# Power_supply.net
KiCad netlist of a schematic drawn in Altium Designer
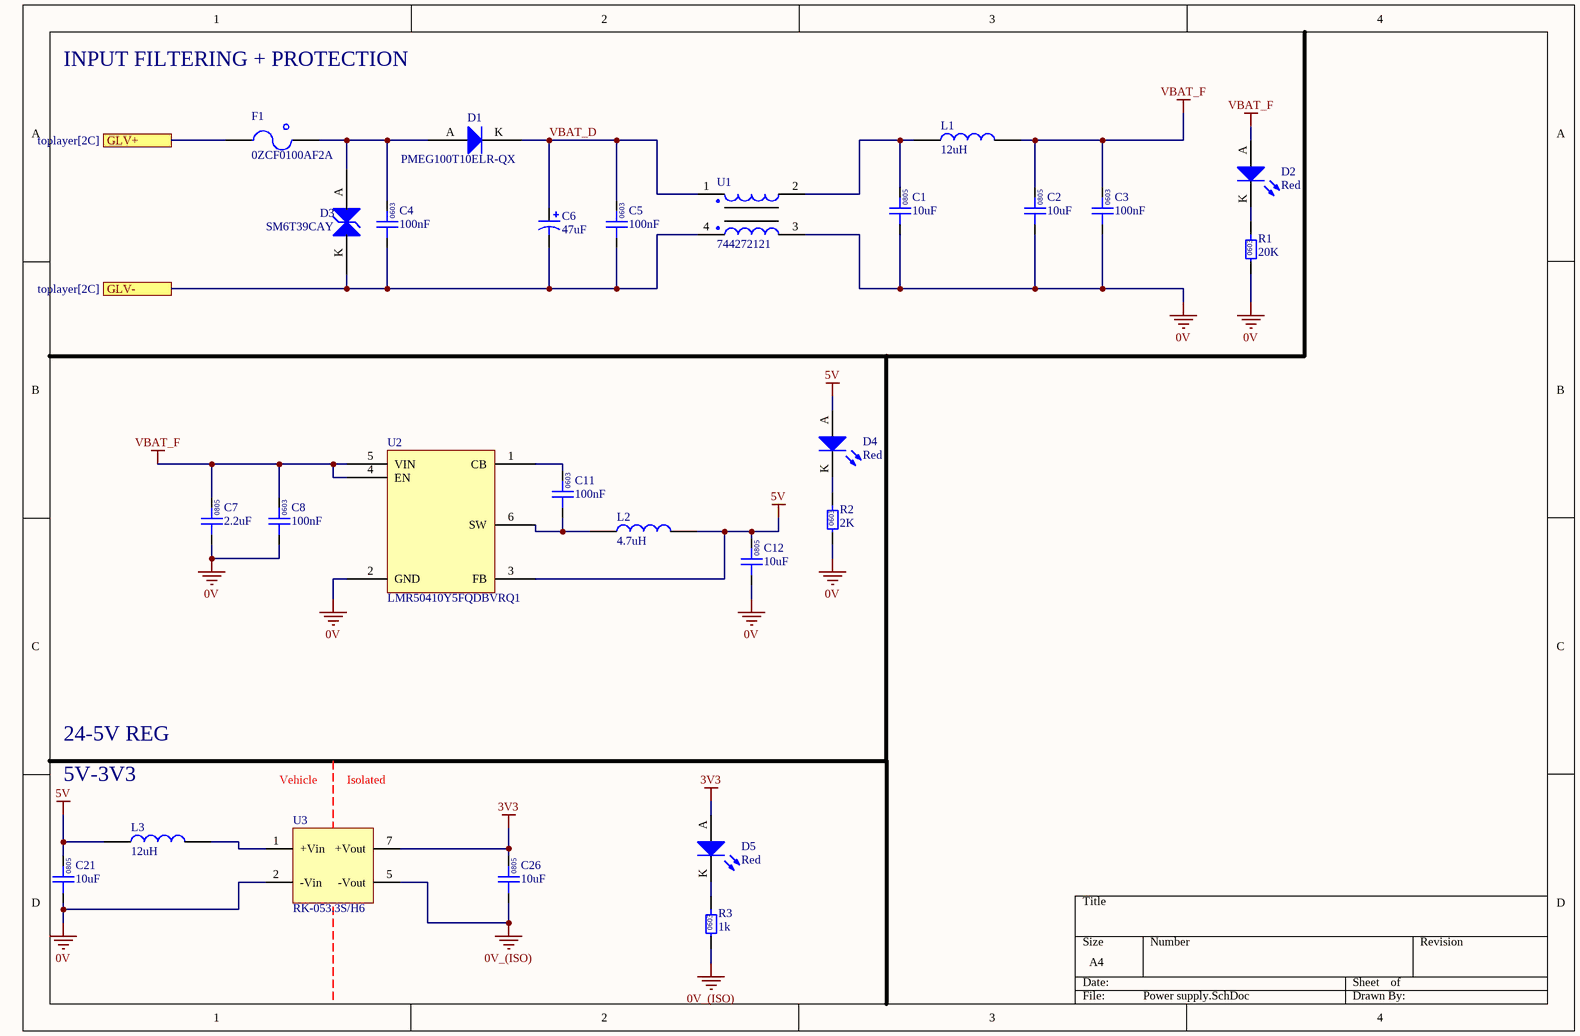
[diagram p0: Power supply.SchDoc]

(export (version "E")
  (design (tool "Eeschema 10.0.6"))
  (components
    (comp (ref "C1")
      (value "10uF")
      (footprint "0805")
      (fields
        (field (name "PART NUMBER") "GRM21BR6YA106KE43L")
        (field (name "MANUFACTURER") "muRata")
        (field (name "TOLERANCE") "10%")
      )
      (libsource (lib "ts_standard_library") (part "Capacitor 0805"))
    )
    (comp (ref "C2")
      (value "10uF")
      (footprint "0805")
      (fields
        (field (name "PART NUMBER") "GRM21BR6YA106KE43L")
        (field (name "MANUFACTURER") "muRata")
        (field (name "TOLERANCE") "10%")
      )
      (libsource (lib "ts_standard_library") (part "Capacitor 0805"))
    )
    (comp (ref "C3")
      (value "100nF")
      (footprint "0603")
      (fields
        (field (name "PART NUMBER") "GCM188L81H104KA57D")
        (field (name "MANUFACTURER") "muRata")
        (field (name "TOLERANCE") "±10%")
      )
      (libsource (lib "ts_standard_library") (part "Capacitor 0603"))
    )
    (comp (ref "C4")
      (value "100nF")
      (footprint "0603")
      (fields
        (field (name "PART NUMBER") "GCM188L81H104KA57D")
        (field (name "MANUFACTURER") "muRata")
        (field (name "TOLERANCE") "±10%")
      )
      (libsource (lib "ts_standard_library") (part "Capacitor 0603"))
    )
    (comp (ref "C5")
      (value "100nF")
      (footprint "0603")
      (fields
        (field (name "PART NUMBER") "GCM188L81H104KA57D")
        (field (name "MANUFACTURER") "muRata")
        (field (name "TOLERANCE") "±10%")
      )
      (libsource (lib "ts_standard_library") (part "Capacitor 0603"))
    )
    (comp (ref "C6")
      (value "47uF")
      (footprint "CHEMI-CON ELCO")
      (fields (field (name "PART NUMBER") "HHXA350ARA470MF61G"))
      (libsource (lib "ts_standard_library") (part "Capacitor (Polarised)"))
    )
    (comp (ref "C7")
      (value "2.2uF")
      (footprint "0805")
      (fields
        (field (name "PART NUMBER") "GRM21BR61A226ME51L")
        (field (name "MANUFACTURER") "muRata")
        (field (name "TOLERANCE") "20%")
      )
      (libsource (lib "ts_standard_library") (part "Capacitor 0805"))
    )
    (comp (ref "C8")
      (value "100nF")
      (footprint "0603")
      (fields
        (field (name "PART NUMBER") "GCM188L81H104KA57D")
        (field (name "MANUFACTURER") "muRata")
        (field (name "TOLERANCE") "±10%")
      )
      (libsource (lib "ts_standard_library") (part "Capacitor 0603"))
    )
    (comp (ref "C11")
      (value "100nF")
      (footprint "0603")
      (fields
        (field (name "PART NUMBER") "GCM188L81H104KA57D")
        (field (name "MANUFACTURER") "muRata")
        (field (name "TOLERANCE") "±10%")
      )
      (libsource (lib "ts_standard_library") (part "Capacitor 0603"))
    )
    (comp (ref "C12")
      (value "10uF")
      (footprint "0805")
      (fields
        (field (name "PART NUMBER") "GRM21BR6YA106KE43L")
        (field (name "MANUFACTURER") "muRata")
        (field (name "TOLERANCE") "10%")
      )
      (libsource (lib "ts_standard_library") (part "Capacitor 0805"))
    )
    (comp (ref "C21")
      (value "10uF")
      (footprint "0805")
      (fields
        (field (name "PART NUMBER") "GRM21BR6YA106KE43L")
        (field (name "MANUFACTURER") "muRata")
        (field (name "TOLERANCE") "10%")
      )
      (libsource (lib "ts_standard_library") (part "Capacitor 0805"))
    )
    (comp (ref "C26")
      (value "10uF")
      (footprint "0805")
      (fields
        (field (name "PART NUMBER") "GRM21BR6YA106KE43L")
        (field (name "MANUFACTURER") "muRata")
        (field (name "TOLERANCE") "10%")
      )
      (libsource (lib "ts_standard_library") (part "Capacitor 0805"))
    )
    (comp (ref "D1")
      (value "PMEG100T10ELR-QX")
      (footprint "SODFL350X110-2N")
      (description "Diode 100 V 1A Surface Mount SOD-123W")
      (libsource (lib "Team Swinburne") (part "PMEG100T10ELR-QX"))
    )
    (comp (ref "D2")
      (value "Red")
      (footprint "0805 LED")
      (description "Red LED Indication - Discrete 1.75V 0805 (2012 Metric)")
      (fields (field (name "PART NUMBER") "SML-210LTT86") (field (name "MANUFACTURER") "ROHM Semiconductor"))
      (libsource (lib "ts_standard_library") (part "LED"))
    )
    (comp (ref "D3")
      (value "SM6T39CAY")
      (footprint "SM6T39CAY-Footprint-1")
      (description "TVS Diode Single Bi-Dir 33.3V 600W Automotive 2-Pin SMB T/R / TVS DIODE 33.3VWM 69.7VC SMB")
      (libsource (lib "Team Swinburne") (part "SM6T39CAY-Symbol"))
    )
    (comp (ref "D4")
      (value "Red")
      (footprint "0805 LED")
      (description "Red LED Indication - Discrete 1.75V 0805 (2012 Metric)")
      (fields (field (name "PART NUMBER") "SML-210LTT86") (field (name "MANUFACTURER") "ROHM Semiconductor"))
      (libsource (lib "ts_standard_library") (part "LED"))
    )
    (comp (ref "D5")
      (value "Red")
      (footprint "0805 LED")
      (description "Red LED Indication - Discrete 1.75V 0805 (2012 Metric)")
      (fields (field (name "PART NUMBER") "SML-210LTT86") (field (name "MANUFACTURER") "ROHM Semiconductor"))
      (libsource (lib "ts_standard_library") (part "LED"))
    )
    (comp (ref "F1")
      (value "0ZCF0100AF2A")
      (footprint "2920")
      (description "PTC RESET FUSE 60V 1A 292")
      (fields
        (field (name "MANUFACTURER") "Littelfuse Inc.")
        (field (name "DIGIKEY PART NUMBER") "507-2070-1-ND")
      )
      (libsource (lib "ts_standard_library") (part "PTC Fuse"))
    )
    (comp (ref "L1")
      (value "12uH")
      (footprint "1812")
      (fields
        (field (name "PART NUMBER") "RLS-126")
        (field (name "MANUFACTURER") "Recom")
        (field (name "TOLERANCE") "0.2")
      )
      (libsource (lib "ts_standard_library") (part "Inductor"))
    )
    (comp (ref "L2")
      (value "4.7uH")
      (footprint "SRN3015TA-4R7M")
      (fields
        (field (name "PART NUMBER") "SRN4018-4R7M")
        (field (name "MANUFACTURER") "Bourns")
        (field (name "TOLERANCE") "0.2")
      )
      (libsource (lib "ts_standard_library") (part "Inductor"))
    )
    (comp (ref "L3")
      (value "12uH")
      (footprint "1812")
      (fields
        (field (name "PART NUMBER") "RLS-126")
        (field (name "MANUFACTURER") "Recom")
        (field (name "TOLERANCE") "0.2")
      )
      (libsource (lib "ts_standard_library") (part "Inductor"))
    )
    (comp (ref "R1")
      (value "20K")
      (footprint "0603")
      (fields
        (field (name "PART NUMBER") "RC0603FR-0720KL")
        (field (name "MANUFACTURER") "YAGEO")
        (field (name "TOLERANCE") "0.01")
      )
      (libsource (lib "ts_standard_library") (part "Resistor 0603"))
    )
    (comp (ref "R2")
      (value "2K")
      (footprint "0603")
      (fields
        (field (name "PART NUMBER") "RC0603FR-072KL")
        (field (name "MANUFACTURER") "YAGEO")
        (field (name "TOLERANCE") "0.01")
      )
      (libsource (lib "ts_standard_library") (part "Resistor 0603"))
    )
    (comp (ref "R3")
      (value "1k")
      (footprint "0603")
      (fields
        (field (name "PART NUMBER") "RC0603FR-071KL")
        (field (name "MANUFACTURER") "YAGEO")
        (field (name "TOLERANCE") "0.01")
      )
      (libsource (lib "ts_standard_library") (part "Resistor 0603"))
    )
    (comp (ref "U1")
      (value "744272121")
      (footprint "Wurth 4-PC Pad")
      (fields
        (field (name "MANUFACTURER") "Wurth Electronics Inc")
        (field (name "DIGIKEY PART NUMBER") "732-1489-1-ND")
      )
      (libsource (lib "ts_standard_library") (part "CM Choke"))
    )
    (comp (ref "U2")
      (value "LMR50410Y5FQDBVRQ1")
      (footprint "TI-SOT23-6")
      (description "IC REG BUCK 5V 1A SOT23-6")
      (fields (field (name "PART NUMBER") "LMR50410-Q1") (field (name "MANUFACTURER") "Texas Instruments"))
      (libsource (lib "ts_standard_library") (part "LMR50410Y5FQDBVRQ1"))
    )
    (comp (ref "U3")
      (value "RK-053.3S/H6")
      (footprint "RK-053.3S/H6")
      (description "DC DC CONVERTER 3.3V 1W")
      (fields (field (name "MANUFACTURER") "Recom"))
      (libsource (lib "ts_standard_library") (part "RK-053.3S/H6"))
    )
  )
  (nets
    (net (code "1") (name "/GLV+") (class "Default")
      (node (ref "F1") (pin "1") (pinfunction "1_1") (pintype "passive"))
    )
    (net (code "2") (name "/GLV-") (class "Default")
      (node (ref "C4") (pin "1") (pinfunction "1_1") (pintype "passive"))
      (node (ref "C5") (pin "1") (pinfunction "1_1") (pintype "passive"))
      (node (ref "C6") (pin "1") (pinfunction "1_1") (pintype "passive"))
      (node (ref "D3") (pin "K") (pintype "passive"))
      (node (ref "U1") (pin "4") (pinfunction "4_4") (pintype "passive"))
    )
    (net (code "3") (name "/VBAT_D") (class "Default")
      (node (ref "C5") (pin "2") (pinfunction "2_2") (pintype "passive"))
      (node (ref "C6") (pin "2") (pinfunction "2_2") (pintype "passive"))
      (node (ref "D1") (pin "K") (pintype "passive"))
      (node (ref "U1") (pin "1") (pinfunction "1_1") (pintype "passive"))
    )
    (net (code "4") (name "0V") (class "Default")
      (node (ref "C1") (pin "1") (pinfunction "1_1") (pintype "passive"))
      (node (ref "C12") (pin "1") (pinfunction "1_1") (pintype "passive"))
      (node (ref "C2") (pin "1") (pinfunction "1_1") (pintype "passive"))
      (node (ref "C21") (pin "1") (pinfunction "1_1") (pintype "passive"))
      (node (ref "C3") (pin "1") (pinfunction "1_1") (pintype "passive"))
      (node (ref "C7") (pin "1") (pinfunction "1_1") (pintype "passive"))
      (node (ref "C8") (pin "1") (pinfunction "1_1") (pintype "passive"))
      (node (ref "R1") (pin "1") (pinfunction "1_1") (pintype "passive"))
      (node (ref "R2") (pin "1") (pinfunction "1_1") (pintype "passive"))
      (node (ref "U1") (pin "3") (pinfunction "3_3") (pintype "power_in"))
      (node (ref "U2") (pin "2") (pinfunction "GND_2") (pintype "passive"))
      (node (ref "U3") (pin "2") (pinfunction "-Vin_2") (pintype "power_in"))
    )
    (net (code "5") (name "0V_(ISO)") (class "Default")
      (node (ref "C26") (pin "1") (pinfunction "1_1") (pintype "passive"))
      (node (ref "R3") (pin "1") (pinfunction "1_1") (pintype "passive"))
      (node (ref "U3") (pin "5") (pinfunction "-Vout_5") (pintype "power_in"))
    )
    (net (code "6") (name "3V3") (class "Default")
      (node (ref "C26") (pin "2") (pinfunction "2_2") (pintype "passive"))
      (node (ref "D5") (pin "A") (pinfunction "A_A") (pintype "passive"))
      (node (ref "U3") (pin "7") (pinfunction "+Vout_7") (pintype "power_in"))
    )
    (net (code "7") (name "5V") (class "Default")
      (node (ref "C12") (pin "2") (pinfunction "2_2") (pintype "passive"))
      (node (ref "C21") (pin "2") (pinfunction "2_2") (pintype "passive"))
      (node (ref "D4") (pin "A") (pinfunction "A_A") (pintype "passive"))
      (node (ref "L2") (pin "1") (pinfunction "1_1") (pintype "passive"))
      (node (ref "L3") (pin "2") (pinfunction "2_2") (pintype "passive"))
      (node (ref "U2") (pin "3") (pinfunction "FB_3") (pintype "passive"))
    )
    (net (code "8") (name "Net-(C1-Pad2)") (class "Default")
      (node (ref "C1") (pin "2") (pinfunction "2_2") (pintype "passive"))
      (node (ref "L1") (pin "2") (pinfunction "2_2") (pintype "passive"))
      (node (ref "U1") (pin "2") (pinfunction "2_2") (pintype "passive"))
    )
    (net (code "9") (name "Net-(C4-Pad2)") (class "Default")
      (node (ref "C4") (pin "2") (pinfunction "2_2") (pintype "passive"))
      (node (ref "D1") (pin "A") (pintype "passive"))
      (node (ref "D3") (pin "A") (pintype "passive"))
      (node (ref "F1") (pin "2") (pinfunction "2_2") (pintype "passive"))
    )
    (net (code "10") (name "Net-(D2-PadK)") (class "Default")
      (node (ref "D2") (pin "K") (pinfunction "K_K") (pintype "passive"))
      (node (ref "R1") (pin "2") (pinfunction "2_2") (pintype "passive"))
    )
    (net (code "11") (name "Net-(D4-PadK)") (class "Default")
      (node (ref "D4") (pin "K") (pinfunction "K_K") (pintype "passive"))
      (node (ref "R2") (pin "2") (pinfunction "2_2") (pintype "passive"))
    )
    (net (code "12") (name "Net-(D5-PadK)") (class "Default")
      (node (ref "D5") (pin "K") (pinfunction "K_K") (pintype "passive"))
      (node (ref "R3") (pin "2") (pinfunction "2_2") (pintype "passive"))
    )
    (net (code "13") (name "Net-(U2-CB)") (class "Default")
      (node (ref "C11") (pin "2") (pinfunction "2_2") (pintype "passive"))
      (node (ref "U2") (pin "1") (pinfunction "CB_1") (pintype "passive"))
    )
    (net (code "14") (name "Net-(U2-SW)") (class "Default")
      (node (ref "C11") (pin "1") (pinfunction "1_1") (pintype "passive"))
      (node (ref "L2") (pin "2") (pinfunction "2_2") (pintype "passive"))
      (node (ref "U2") (pin "6") (pinfunction "SW_6") (pintype "passive"))
    )
    (net (code "15") (name "Net-(U3-+Vin)") (class "Default")
      (node (ref "L3") (pin "1") (pinfunction "1_1") (pintype "passive"))
      (node (ref "U3") (pin "1") (pinfunction "+Vin_1") (pintype "power_in"))
    )
    (net (code "16") (name "VBAT_F") (class "Default")
      (node (ref "C2") (pin "2") (pinfunction "2_2") (pintype "passive"))
      (node (ref "C3") (pin "2") (pinfunction "2_2") (pintype "passive"))
      (node (ref "C7") (pin "2") (pinfunction "2_2") (pintype "passive"))
      (node (ref "C8") (pin "2") (pinfunction "2_2") (pintype "passive"))
      (node (ref "D2") (pin "A") (pinfunction "A_A") (pintype "passive"))
      (node (ref "L1") (pin "1") (pinfunction "1_1") (pintype "passive"))
      (node (ref "U2") (pin "4") (pinfunction "EN_4") (pintype "passive"))
      (node (ref "U2") (pin "5") (pinfunction "VIN_5") (pintype "passive"))
    )
  )
)
